# nixie_light.net
KiCad netlist of a schematic drawn in Altium Designer
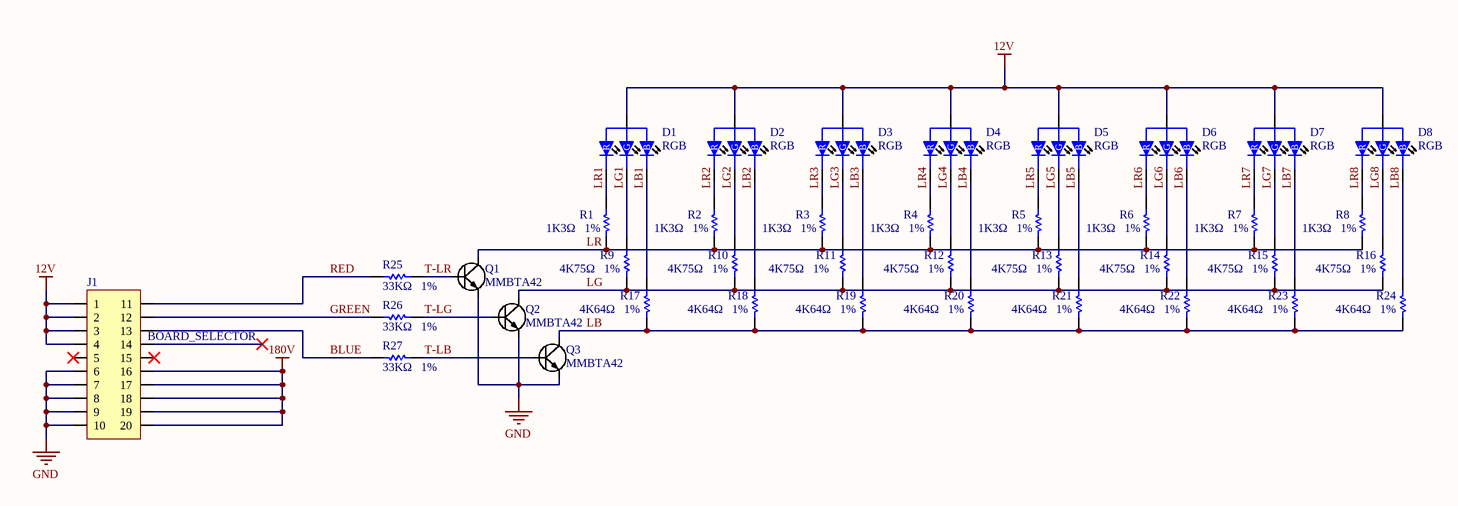
[diagram p0: nixie_light.SchDoc]

(export (version "E")
  (design (tool "Eeschema 10.0.6"))
  (components
    (comp (ref "D1")
      (value "RGB")
      (footprint "1210-RGB")
      (description "qblp655-rgb")
      (libsource (lib "MyLib") (part "RGB"))
    )
    (comp (ref "D2")
      (value "RGB")
      (footprint "1210-RGB")
      (description "qblp655-rgb")
      (libsource (lib "MyLib") (part "RGB"))
    )
    (comp (ref "D3")
      (value "RGB")
      (footprint "1210-RGB")
      (description "qblp655-rgb")
      (libsource (lib "MyLib") (part "RGB"))
    )
    (comp (ref "D4")
      (value "RGB")
      (footprint "1210-RGB")
      (description "qblp655-rgb")
      (libsource (lib "MyLib") (part "RGB"))
    )
    (comp (ref "D5")
      (value "RGB")
      (footprint "1210-RGB")
      (description "qblp655-rgb")
      (libsource (lib "MyLib") (part "RGB"))
    )
    (comp (ref "D6")
      (value "RGB")
      (footprint "1210-RGB")
      (description "qblp655-rgb")
      (libsource (lib "MyLib") (part "RGB"))
    )
    (comp (ref "D7")
      (value "RGB")
      (footprint "1210-RGB")
      (description "qblp655-rgb")
      (libsource (lib "MyLib") (part "RGB"))
    )
    (comp (ref "D8")
      (value "RGB")
      (footprint "1210-RGB")
      (description "qblp655-rgb")
      (libsource (lib "MyLib") (part "RGB"))
    )
    (comp (ref "J1")
      (value "PIN_2X10")
      (footprint "PIN_2X10_HDR")
      (description "TSW-110-15-F-D-LL")
      (libsource (lib "Nixielib") (part "PIN_2X10"))
    )
    (comp (ref "Q1") (value "MMBTA42") (footprint "SOT-23") (libsource (lib "Nixielib") (part "NPN")))
    (comp (ref "Q2") (value "MMBTA42") (footprint "SOT-23") (libsource (lib "Nixielib") (part "NPN")))
    (comp (ref "Q3") (value "MMBTA42") (footprint "SOT-23") (libsource (lib "Nixielib") (part "NPN")))
    (comp (ref "R1") (value "1K3Ω   1%") (footprint "0603") (libsource (lib "Nixielib") (part "RES")))
    (comp (ref "R2") (value "1K3Ω   1%") (footprint "0603") (libsource (lib "Nixielib") (part "RES")))
    (comp (ref "R3") (value "1K3Ω   1%") (footprint "0603") (libsource (lib "Nixielib") (part "RES")))
    (comp (ref "R4") (value "1K3Ω   1%") (footprint "0603") (libsource (lib "Nixielib") (part "RES")))
    (comp (ref "R5") (value "1K3Ω   1%") (footprint "0603") (libsource (lib "Nixielib") (part "RES")))
    (comp (ref "R6") (value "1K3Ω   1%") (footprint "0603") (libsource (lib "Nixielib") (part "RES")))
    (comp (ref "R7") (value "1K3Ω   1%") (footprint "0603") (libsource (lib "Nixielib") (part "RES")))
    (comp (ref "R8") (value "1K3Ω   1%") (footprint "0603") (libsource (lib "Nixielib") (part "RES")))
    (comp (ref "R9") (value "4K75Ω   1%") (footprint "0603") (libsource (lib "Nixielib") (part "RES")))
    (comp (ref "R10") (value "4K75Ω   1%") (footprint "0603") (libsource (lib "Nixielib") (part "RES")))
    (comp (ref "R11") (value "4K75Ω   1%") (footprint "0603") (libsource (lib "Nixielib") (part "RES")))
    (comp (ref "R12") (value "4K75Ω   1%") (footprint "0603") (libsource (lib "Nixielib") (part "RES")))
    (comp (ref "R13") (value "4K75Ω   1%") (footprint "0603") (libsource (lib "Nixielib") (part "RES")))
    (comp (ref "R14") (value "4K75Ω   1%") (footprint "0603") (libsource (lib "Nixielib") (part "RES")))
    (comp (ref "R15") (value "4K75Ω   1%") (footprint "0603") (libsource (lib "Nixielib") (part "RES")))
    (comp (ref "R16") (value "4K75Ω   1%") (footprint "0603") (libsource (lib "Nixielib") (part "RES")))
    (comp (ref "R17") (value "4K64Ω   1%") (footprint "0603") (libsource (lib "Nixielib") (part "RES")))
    (comp (ref "R18") (value "4K64Ω   1%") (footprint "0603") (libsource (lib "Nixielib") (part "RES")))
    (comp (ref "R19") (value "4K64Ω   1%") (footprint "0603") (libsource (lib "Nixielib") (part "RES")))
    (comp (ref "R20") (value "4K64Ω   1%") (footprint "0603") (libsource (lib "Nixielib") (part "RES")))
    (comp (ref "R21") (value "4K64Ω   1%") (footprint "0603") (libsource (lib "Nixielib") (part "RES")))
    (comp (ref "R22") (value "4K64Ω   1%") (footprint "0603") (libsource (lib "Nixielib") (part "RES")))
    (comp (ref "R23") (value "4K64Ω   1%") (footprint "0603") (libsource (lib "Nixielib") (part "RES")))
    (comp (ref "R24") (value "4K64Ω   1%") (footprint "0603") (libsource (lib "Nixielib") (part "RES")))
    (comp (ref "R25") (value "33KΩ   1%") (footprint "0603") (libsource (lib "Nixielib") (part "RES")))
    (comp (ref "R26") (value "33KΩ   1%") (footprint "0603") (libsource (lib "Nixielib") (part "RES")))
    (comp (ref "R27") (value "33KΩ   1%") (footprint "0603") (libsource (lib "Nixielib") (part "RES")))
  )
  (nets
    (net (code "1") (name "/BLUE") (class "Default")
      (node (ref "J1") (pin "13") (pinfunction "13_13") (pintype "passive"))
      (node (ref "R27") (pin "1") (pinfunction "1_1") (pintype "passive"))
    )
    (net (code "2") (name "/GREEN") (class "Default")
      (node (ref "J1") (pin "12") (pinfunction "12_12") (pintype "passive"))
      (node (ref "R26") (pin "1") (pinfunction "1_1") (pintype "passive"))
    )
    (net (code "3") (name "/LB") (class "Default")
      (node (ref "Q3") (pin "3") (pinfunction "C_3") (pintype "passive"))
      (node (ref "R17") (pin "1") (pinfunction "1_1") (pintype "passive"))
      (node (ref "R18") (pin "1") (pinfunction "1_1") (pintype "passive"))
      (node (ref "R19") (pin "1") (pinfunction "1_1") (pintype "passive"))
      (node (ref "R20") (pin "1") (pinfunction "1_1") (pintype "passive"))
      (node (ref "R21") (pin "1") (pinfunction "1_1") (pintype "passive"))
      (node (ref "R22") (pin "1") (pinfunction "1_1") (pintype "passive"))
      (node (ref "R23") (pin "1") (pinfunction "1_1") (pintype "passive"))
      (node (ref "R24") (pin "1") (pinfunction "1_1") (pintype "passive"))
    )
    (net (code "4") (name "/LB1") (class "Default")
      (node (ref "D1") (pin "3") (pinfunction "B_3") (pintype "passive"))
      (node (ref "R17") (pin "2") (pinfunction "2_2") (pintype "passive"))
    )
    (net (code "5") (name "/LB2") (class "Default")
      (node (ref "D2") (pin "3") (pinfunction "B_3") (pintype "passive"))
      (node (ref "R18") (pin "2") (pinfunction "2_2") (pintype "passive"))
    )
    (net (code "6") (name "/LB3") (class "Default")
      (node (ref "D3") (pin "3") (pinfunction "B_3") (pintype "passive"))
      (node (ref "R19") (pin "2") (pinfunction "2_2") (pintype "passive"))
    )
    (net (code "7") (name "/LB4") (class "Default")
      (node (ref "D4") (pin "3") (pinfunction "B_3") (pintype "passive"))
      (node (ref "R20") (pin "2") (pinfunction "2_2") (pintype "passive"))
    )
    (net (code "8") (name "/LB5") (class "Default")
      (node (ref "D5") (pin "3") (pinfunction "B_3") (pintype "passive"))
      (node (ref "R21") (pin "2") (pinfunction "2_2") (pintype "passive"))
    )
    (net (code "9") (name "/LB6") (class "Default")
      (node (ref "D6") (pin "3") (pinfunction "B_3") (pintype "passive"))
      (node (ref "R22") (pin "2") (pinfunction "2_2") (pintype "passive"))
    )
    (net (code "10") (name "/LB7") (class "Default")
      (node (ref "D7") (pin "3") (pinfunction "B_3") (pintype "passive"))
      (node (ref "R23") (pin "2") (pinfunction "2_2") (pintype "passive"))
    )
    (net (code "11") (name "/LB8") (class "Default")
      (node (ref "D8") (pin "3") (pinfunction "B_3") (pintype "passive"))
      (node (ref "R24") (pin "2") (pinfunction "2_2") (pintype "passive"))
    )
    (net (code "12") (name "/LG") (class "Default")
      (node (ref "Q2") (pin "3") (pinfunction "C_3") (pintype "passive"))
      (node (ref "R10") (pin "1") (pinfunction "1_1") (pintype "passive"))
      (node (ref "R11") (pin "1") (pinfunction "1_1") (pintype "passive"))
      (node (ref "R12") (pin "1") (pinfunction "1_1") (pintype "passive"))
      (node (ref "R13") (pin "1") (pinfunction "1_1") (pintype "passive"))
      (node (ref "R14") (pin "1") (pinfunction "1_1") (pintype "passive"))
      (node (ref "R15") (pin "1") (pinfunction "1_1") (pintype "passive"))
      (node (ref "R16") (pin "1") (pinfunction "1_1") (pintype "passive"))
      (node (ref "R9") (pin "1") (pinfunction "1_1") (pintype "passive"))
    )
    (net (code "13") (name "/LG1") (class "Default")
      (node (ref "D1") (pin "4") (pinfunction "G_4") (pintype "passive"))
      (node (ref "R9") (pin "2") (pinfunction "2_2") (pintype "passive"))
    )
    (net (code "14") (name "/LG2") (class "Default")
      (node (ref "D2") (pin "4") (pinfunction "G_4") (pintype "passive"))
      (node (ref "R10") (pin "2") (pinfunction "2_2") (pintype "passive"))
    )
    (net (code "15") (name "/LG3") (class "Default")
      (node (ref "D3") (pin "4") (pinfunction "G_4") (pintype "passive"))
      (node (ref "R11") (pin "2") (pinfunction "2_2") (pintype "passive"))
    )
    (net (code "16") (name "/LG4") (class "Default")
      (node (ref "D4") (pin "4") (pinfunction "G_4") (pintype "passive"))
      (node (ref "R12") (pin "2") (pinfunction "2_2") (pintype "passive"))
    )
    (net (code "17") (name "/LG5") (class "Default")
      (node (ref "D5") (pin "4") (pinfunction "G_4") (pintype "passive"))
      (node (ref "R13") (pin "2") (pinfunction "2_2") (pintype "passive"))
    )
    (net (code "18") (name "/LG6") (class "Default")
      (node (ref "D6") (pin "4") (pinfunction "G_4") (pintype "passive"))
      (node (ref "R14") (pin "2") (pinfunction "2_2") (pintype "passive"))
    )
    (net (code "19") (name "/LG7") (class "Default")
      (node (ref "D7") (pin "4") (pinfunction "G_4") (pintype "passive"))
      (node (ref "R15") (pin "2") (pinfunction "2_2") (pintype "passive"))
    )
    (net (code "20") (name "/LG8") (class "Default")
      (node (ref "D8") (pin "4") (pinfunction "G_4") (pintype "passive"))
      (node (ref "R16") (pin "2") (pinfunction "2_2") (pintype "passive"))
    )
    (net (code "21") (name "/LR") (class "Default")
      (node (ref "Q1") (pin "3") (pinfunction "C_3") (pintype "passive"))
      (node (ref "R1") (pin "1") (pinfunction "1_1") (pintype "passive"))
      (node (ref "R2") (pin "1") (pinfunction "1_1") (pintype "passive"))
      (node (ref "R3") (pin "1") (pinfunction "1_1") (pintype "passive"))
      (node (ref "R4") (pin "1") (pinfunction "1_1") (pintype "passive"))
      (node (ref "R5") (pin "1") (pinfunction "1_1") (pintype "passive"))
      (node (ref "R6") (pin "1") (pinfunction "1_1") (pintype "passive"))
      (node (ref "R7") (pin "1") (pinfunction "1_1") (pintype "passive"))
      (node (ref "R8") (pin "1") (pinfunction "1_1") (pintype "passive"))
    )
    (net (code "22") (name "/LR1") (class "Default")
      (node (ref "D1") (pin "1") (pinfunction "R_1") (pintype "passive"))
      (node (ref "R1") (pin "2") (pinfunction "2_2") (pintype "passive"))
    )
    (net (code "23") (name "/LR2") (class "Default")
      (node (ref "D2") (pin "1") (pinfunction "R_1") (pintype "passive"))
      (node (ref "R2") (pin "2") (pinfunction "2_2") (pintype "passive"))
    )
    (net (code "24") (name "/LR3") (class "Default")
      (node (ref "D3") (pin "1") (pinfunction "R_1") (pintype "passive"))
      (node (ref "R3") (pin "2") (pinfunction "2_2") (pintype "passive"))
    )
    (net (code "25") (name "/LR4") (class "Default")
      (node (ref "D4") (pin "1") (pinfunction "R_1") (pintype "passive"))
      (node (ref "R4") (pin "2") (pinfunction "2_2") (pintype "passive"))
    )
    (net (code "26") (name "/LR5") (class "Default")
      (node (ref "D5") (pin "1") (pinfunction "R_1") (pintype "passive"))
      (node (ref "R5") (pin "2") (pinfunction "2_2") (pintype "passive"))
    )
    (net (code "27") (name "/LR6") (class "Default")
      (node (ref "D6") (pin "1") (pinfunction "R_1") (pintype "passive"))
      (node (ref "R6") (pin "2") (pinfunction "2_2") (pintype "passive"))
    )
    (net (code "28") (name "/LR7") (class "Default")
      (node (ref "D7") (pin "1") (pinfunction "R_1") (pintype "passive"))
      (node (ref "R7") (pin "2") (pinfunction "2_2") (pintype "passive"))
    )
    (net (code "29") (name "/LR8") (class "Default")
      (node (ref "D8") (pin "1") (pinfunction "R_1") (pintype "passive"))
      (node (ref "R8") (pin "2") (pinfunction "2_2") (pintype "passive"))
    )
    (net (code "30") (name "/RED") (class "Default")
      (node (ref "J1") (pin "11") (pinfunction "11_11") (pintype "passive"))
      (node (ref "R25") (pin "1") (pinfunction "1_1") (pintype "passive"))
    )
    (net (code "31") (name "/T-LB") (class "Default")
      (node (ref "Q3") (pin "1") (pinfunction "B_1") (pintype "passive"))
      (node (ref "R27") (pin "2") (pinfunction "2_2") (pintype "passive"))
    )
    (net (code "32") (name "/T-LG") (class "Default")
      (node (ref "Q2") (pin "1") (pinfunction "B_1") (pintype "passive"))
      (node (ref "R26") (pin "2") (pinfunction "2_2") (pintype "passive"))
    )
    (net (code "33") (name "/T-LR") (class "Default")
      (node (ref "Q1") (pin "1") (pinfunction "B_1") (pintype "passive"))
      (node (ref "R25") (pin "2") (pinfunction "2_2") (pintype "passive"))
    )
    (net (code "34") (name "12V") (class "Default")
      (node (ref "D1") (pin "2") (pinfunction "A_2") (pintype "passive"))
      (node (ref "D2") (pin "2") (pinfunction "A_2") (pintype "passive"))
      (node (ref "D3") (pin "2") (pinfunction "A_2") (pintype "passive"))
      (node (ref "D4") (pin "2") (pinfunction "A_2") (pintype "passive"))
      (node (ref "D5") (pin "2") (pinfunction "A_2") (pintype "passive"))
      (node (ref "D6") (pin "2") (pinfunction "A_2") (pintype "passive"))
      (node (ref "D7") (pin "2") (pinfunction "A_2") (pintype "passive"))
      (node (ref "D8") (pin "2") (pinfunction "A_2") (pintype "passive"))
      (node (ref "J1") (pin "1") (pinfunction "1_1") (pintype "passive"))
      (node (ref "J1") (pin "2") (pinfunction "2_2") (pintype "passive"))
      (node (ref "J1") (pin "3") (pinfunction "3_3") (pintype "passive"))
      (node (ref "J1") (pin "4") (pinfunction "4_4") (pintype "passive"))
    )
    (net (code "35") (name "180V") (class "Default")
      (node (ref "J1") (pin "16") (pinfunction "16_16") (pintype "passive"))
      (node (ref "J1") (pin "17") (pinfunction "17_17") (pintype "passive"))
      (node (ref "J1") (pin "18") (pinfunction "18_18") (pintype "passive"))
      (node (ref "J1") (pin "19") (pinfunction "19_19") (pintype "passive"))
      (node (ref "J1") (pin "20") (pinfunction "20_20") (pintype "passive"))
    )
    (net (code "36") (name "GND") (class "Default")
      (node (ref "J1") (pin "10") (pinfunction "10_10") (pintype "passive"))
      (node (ref "J1") (pin "6") (pinfunction "6_6") (pintype "passive"))
      (node (ref "J1") (pin "7") (pinfunction "7_7") (pintype "passive"))
      (node (ref "J1") (pin "8") (pinfunction "8_8") (pintype "passive"))
      (node (ref "J1") (pin "9") (pinfunction "9_9") (pintype "passive"))
      (node (ref "Q1") (pin "2") (pinfunction "E_2") (pintype "passive"))
      (node (ref "Q2") (pin "2") (pinfunction "E_2") (pintype "passive"))
      (node (ref "Q3") (pin "2") (pinfunction "E_2") (pintype "passive"))
    )
    (net (code "37") (name "unconnected-(J1-Pad5)") (class "Default")
      (node (ref "J1") (pin "5") (pinfunction "5_5") (pintype "passive+no_connect"))
    )
    (net (code "38") (name "unconnected-(J1-Pad14)") (class "Default")
      (node (ref "J1") (pin "14") (pinfunction "14_14") (pintype "passive+no_connect"))
    )
    (net (code "39") (name "unconnected-(J1-Pad15)") (class "Default")
      (node (ref "J1") (pin "15") (pinfunction "15_15") (pintype "passive+no_connect"))
    )
  )
)
